# SparkFun_VoiceBox_Shield.net
KiCad netlist of a schematic drawn in EAGLE
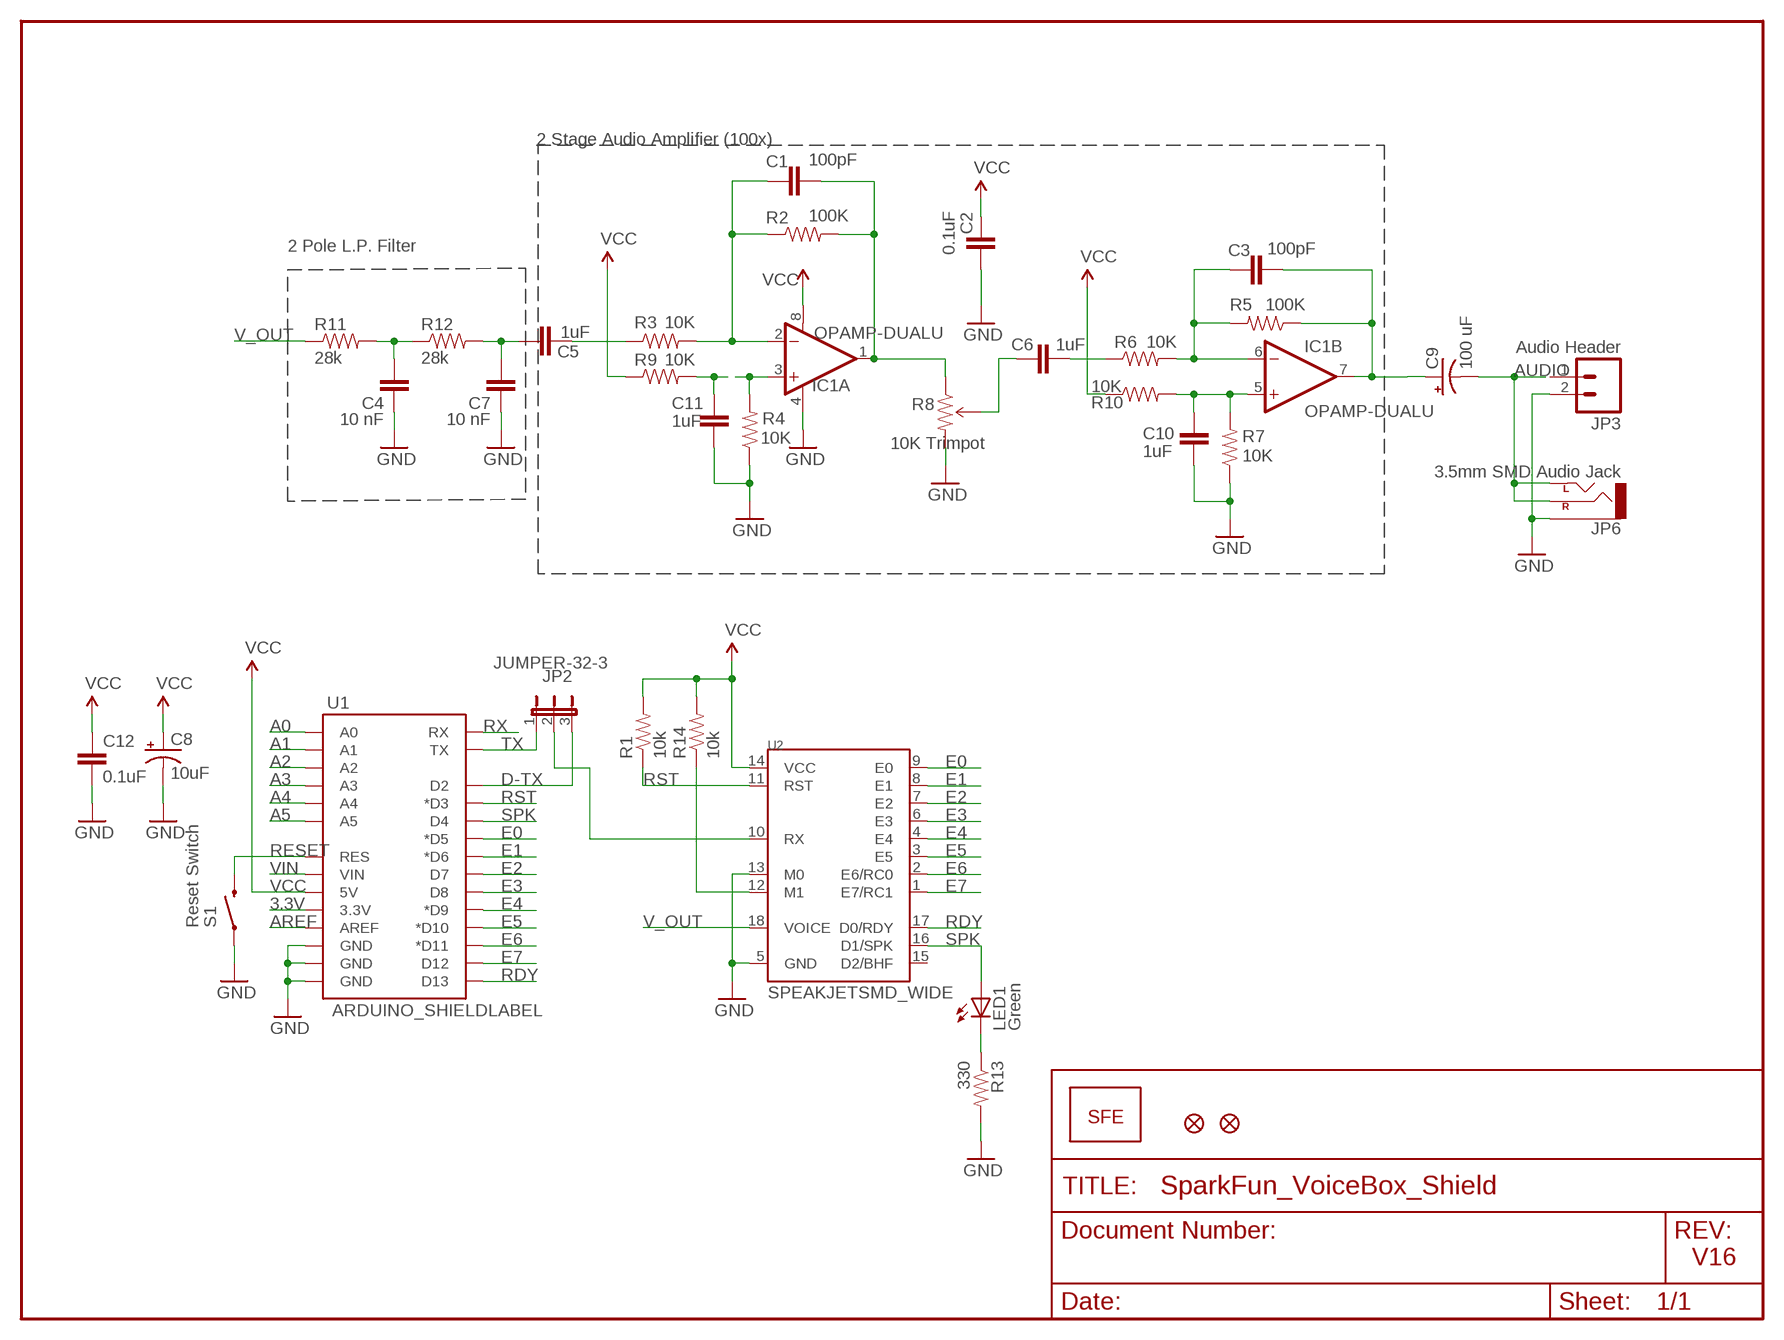
[diagram p0: schematic, sheet 1]

(export (version "E")
  (design (tool "Eeschema 10.0.6"))
  (components
    (comp (ref "C1")
      (value "100pF")
      (footprint "eagle-import:0603-CAP")
      (libsource (lib "eagle-import") (part "CAP0603-CAP"))
    )
    (comp (ref "C2")
      (value "0.1uF")
      (footprint "eagle-import:0603-CAP")
      (libsource (lib "eagle-import") (part "CAP0603-CAP"))
    )
    (comp (ref "C3")
      (value "100pF")
      (footprint "eagle-import:0603-CAP")
      (libsource (lib "eagle-import") (part "CAP0603-CAP"))
    )
    (comp (ref "C4")
      (value "10 nF")
      (footprint "eagle-import:0603-CAP")
      (libsource (lib "eagle-import") (part "CAP0603-CAP"))
    )
    (comp (ref "C5")
      (value "1uF")
      (footprint "eagle-import:0603-CAP")
      (libsource (lib "eagle-import") (part "CAP0603-CAP"))
    )
    (comp (ref "C6")
      (value "1uF")
      (footprint "eagle-import:0603-CAP")
      (libsource (lib "eagle-import") (part "CAP0603-CAP"))
    )
    (comp (ref "C7")
      (value "10 nF")
      (footprint "eagle-import:0603-CAP")
      (libsource (lib "eagle-import") (part "CAP0603-CAP"))
    )
    (comp (ref "C8")
      (value "10uF")
      (footprint "eagle-import:EIA3216")
      (libsource (lib "eagle-import") (part "CAP_POL1206"))
    )
    (comp (ref "C9")
      (value "100 uF")
      (footprint "eagle-import:EIA7343")
      (libsource (lib "eagle-import") (part "CAP_POL7343"))
    )
    (comp (ref "C10")
      (value "1uF")
      (footprint "eagle-import:0603-CAP")
      (libsource (lib "eagle-import") (part "CAP0603-CAP"))
    )
    (comp (ref "C11")
      (value "1uF")
      (footprint "eagle-import:0603-CAP")
      (libsource (lib "eagle-import") (part "CAP0603-CAP"))
    )
    (comp (ref "C12")
      (value "0.1uF")
      (footprint "eagle-import:0603-CAP")
      (libsource (lib "eagle-import") (part "CAP0603-CAP"))
    )
    (comp (ref "IC1")
      (value "OPAMP-DUALU")
      (footprint "eagle-import:SO08")
      (libsource (lib "eagle-import") (part "OPAMP-DUALU"))
    )
    (comp (ref "JP1")
      (value "LOGO-SFENEW")
      (footprint "eagle-import:SFE-NEW-WEBLOGO")
      (libsource (lib "eagle-import") (part "LOGO-SFENEW"))
    )
    (comp (ref "JP2")
      (value "JUMPER-32-3")
      (footprint "eagle-import:SJ_3_PASTE2&3")
      (libsource (lib "eagle-import") (part "JUMPER-32-3"))
    )
    (comp (ref "JP3")
      (value "Audio Header")
      (footprint "eagle-import:1X02")
      (libsource (lib "eagle-import") (part "M02PTH"))
    )
    (comp (ref "JP4")
      (value "FIDUCIAL1X2")
      (footprint "eagle-import:FIDUCIAL-1X2")
      (libsource (lib "eagle-import") (part "FIDUCIAL1X2"))
    )
    (comp (ref "JP5")
      (value "FIDUCIAL1X2")
      (footprint "eagle-import:FIDUCIAL-1X2")
      (libsource (lib "eagle-import") (part "FIDUCIAL1X2"))
    )
    (comp (ref "JP6")
      (value "3.5mm SMD Audio Jack")
      (footprint "eagle-import:AUDIO-JACK-3.5MM-SMD")
      (libsource (lib "eagle-import") (part "AUDIO-JACKSMD2"))
    )
    (comp (ref "LED1")
      (value "Green")
      (footprint "eagle-import:LED-0603")
      (libsource (lib "eagle-import") (part "LED0603"))
    )
    (comp (ref "R1")
      (value "10k")
      (footprint "eagle-import:0603-RES")
      (libsource (lib "eagle-import") (part "RESISTOR0603-RES"))
    )
    (comp (ref "R2")
      (value "100K")
      (footprint "eagle-import:0603-RES")
      (libsource (lib "eagle-import") (part "RESISTOR0603-RES"))
    )
    (comp (ref "R3")
      (value "10K")
      (footprint "eagle-import:0603-RES")
      (libsource (lib "eagle-import") (part "RESISTOR0603-RES"))
    )
    (comp (ref "R4")
      (value "10K")
      (footprint "eagle-import:0603-RES")
      (libsource (lib "eagle-import") (part "RESISTOR0603-RES"))
    )
    (comp (ref "R5")
      (value "100K")
      (footprint "eagle-import:0603-RES")
      (libsource (lib "eagle-import") (part "RESISTOR0603-RES"))
    )
    (comp (ref "R6")
      (value "10K")
      (footprint "eagle-import:0603-RES")
      (libsource (lib "eagle-import") (part "RESISTOR0603-RES"))
    )
    (comp (ref "R7")
      (value "10K")
      (footprint "eagle-import:0603-RES")
      (libsource (lib "eagle-import") (part "RESISTOR0603-RES"))
    )
    (comp (ref "R8")
      (value "10K Trimpot")
      (footprint "eagle-import:TRIMPOT-3MM")
      (libsource (lib "eagle-import") (part "TRIMPOTSMD"))
    )
    (comp (ref "R9")
      (value "10K")
      (footprint "eagle-import:0603")
      (libsource (lib "eagle-import") (part "RESISTOR0603"))
    )
    (comp (ref "R10")
      (value "10K")
      (footprint "eagle-import:0603")
      (libsource (lib "eagle-import") (part "RESISTOR0603"))
    )
    (comp (ref "R11")
      (value "28k")
      (footprint "eagle-import:0603-RES")
      (libsource (lib "eagle-import") (part "RESISTOR0603-RES"))
    )
    (comp (ref "R12")
      (value "28k")
      (footprint "eagle-import:0603-RES")
      (libsource (lib "eagle-import") (part "RESISTOR0603-RES"))
    )
    (comp (ref "R13")
      (value "330")
      (footprint "eagle-import:0603-RES")
      (libsource (lib "eagle-import") (part "RESISTOR0603-RES"))
    )
    (comp (ref "R14")
      (value "10k")
      (footprint "eagle-import:0603-RES")
      (libsource (lib "eagle-import") (part "RESISTOR0603-RES"))
    )
    (comp (ref "S1")
      (value "Reset Switch")
      (footprint "eagle-import:TACTILE_SWITCH_SMD")
      (libsource (lib "eagle-import") (part "SWITCH-MOMENTARY-2SMD"))
    )
    (comp (ref "U1")
      (value "ARDUINO_SHIELDLABEL")
      (footprint "eagle-import:DUEMILANOVE_SHIELD")
      (libsource (lib "eagle-import") (part "ARDUINO_SHIELDLABEL"))
    )
    (comp (ref "U2")
      (value "SPEAKJETSMD_WIDE")
      (footprint "eagle-import:SO-18W")
      (libsource (lib "eagle-import") (part "SPEAKJETSMD_WIDE"))
    )
  )
  (nets
    (net (code "1") (name "/3.3V") (class "Default")
      (node (ref "U1") (pin "3.3V") (pinfunction "3.3V_3.3V") (pintype "bidirectional"))
    )
    (net (code "2") (name "/A0") (class "Default")
      (node (ref "U1") (pin "A0") (pinfunction "A0_A0") (pintype "bidirectional"))
    )
    (net (code "3") (name "/A1") (class "Default")
      (node (ref "U1") (pin "A1") (pinfunction "A1_A1") (pintype "bidirectional"))
    )
    (net (code "4") (name "/A2") (class "Default")
      (node (ref "U1") (pin "A2") (pinfunction "A2_A2") (pintype "bidirectional"))
    )
    (net (code "5") (name "/A3") (class "Default")
      (node (ref "U1") (pin "A3") (pinfunction "A3_A3") (pintype "bidirectional"))
    )
    (net (code "6") (name "/A4") (class "Default")
      (node (ref "U1") (pin "A4") (pinfunction "A4_A4") (pintype "bidirectional"))
    )
    (net (code "7") (name "/A5") (class "Default")
      (node (ref "U1") (pin "A5") (pinfunction "A5_A5") (pintype "bidirectional"))
    )
    (net (code "8") (name "/AREF") (class "Default")
      (node (ref "U1") (pin "AREF") (pinfunction "AREF_AREF") (pintype "bidirectional"))
    )
    (net (code "9") (name "/AUDIO") (class "Default")
      (node (ref "C9") (pin "C") (pinfunction "-_C") (pintype "passive"))
      (node (ref "JP3") (pin "1") (pinfunction "1_1") (pintype "passive"))
      (node (ref "JP6") (pin "RING") (pinfunction "RIGHT_RING") (pintype "bidirectional"))
      (node (ref "JP6") (pin "TIP") (pinfunction "LEFT_TIP") (pintype "bidirectional"))
    )
    (net (code "10") (name "/D-TX") (class "Default")
      (node (ref "JP2") (pin "3") (pinfunction "3_3") (pintype "passive"))
      (node (ref "U1") (pin "D2") (pinfunction "D2_D2") (pintype "bidirectional"))
    )
    (net (code "11") (name "/E0") (class "Default")
      (node (ref "U1") (pin "D5") (pinfunction "*D5_D5") (pintype "bidirectional"))
      (node (ref "U2") (pin "9") (pinfunction "E0_9") (pintype "bidirectional"))
    )
    (net (code "12") (name "/E1") (class "Default")
      (node (ref "U1") (pin "D6") (pinfunction "*D6_D6") (pintype "bidirectional"))
      (node (ref "U2") (pin "8") (pinfunction "E1_8") (pintype "bidirectional"))
    )
    (net (code "13") (name "/E2") (class "Default")
      (node (ref "U1") (pin "D7") (pinfunction "D7_D7") (pintype "bidirectional"))
      (node (ref "U2") (pin "7") (pinfunction "E2_7") (pintype "bidirectional"))
    )
    (net (code "14") (name "/E3") (class "Default")
      (node (ref "U1") (pin "D8") (pinfunction "D8_D8") (pintype "bidirectional"))
      (node (ref "U2") (pin "6") (pinfunction "E3_6") (pintype "bidirectional"))
    )
    (net (code "15") (name "/E4") (class "Default")
      (node (ref "U1") (pin "D9") (pinfunction "*D9_D9") (pintype "bidirectional"))
      (node (ref "U2") (pin "4") (pinfunction "E4_4") (pintype "bidirectional"))
    )
    (net (code "16") (name "/E5") (class "Default")
      (node (ref "U1") (pin "D10") (pinfunction "*D10_D10") (pintype "bidirectional"))
      (node (ref "U2") (pin "3") (pinfunction "E5_3") (pintype "bidirectional"))
    )
    (net (code "17") (name "/E6") (class "Default")
      (node (ref "U1") (pin "D11") (pinfunction "*D11_D11") (pintype "bidirectional"))
      (node (ref "U2") (pin "2") (pinfunction "E6/RC0_2") (pintype "bidirectional"))
    )
    (net (code "18") (name "/E7") (class "Default")
      (node (ref "U1") (pin "D12") (pinfunction "D12_D12") (pintype "bidirectional"))
      (node (ref "U2") (pin "1") (pinfunction "E7/RC1_1") (pintype "bidirectional"))
    )
    (net (code "19") (name "/RDY") (class "Default")
      (node (ref "U1") (pin "D13") (pinfunction "D13_D13") (pintype "bidirectional"))
      (node (ref "U2") (pin "17") (pinfunction "D0/RDY_17") (pintype "bidirectional"))
    )
    (net (code "20") (name "/RESET") (class "Default")
      (node (ref "S1") (pin "3") (pinfunction "2_3") (pintype "passive"))
      (node (ref "U1") (pin "RES") (pinfunction "RES_RES") (pintype "bidirectional"))
    )
    (net (code "21") (name "/RST") (class "Default")
      (node (ref "R1") (pin "1") (pinfunction "1_1") (pintype "passive"))
      (node (ref "U1") (pin "D3") (pinfunction "*D3_D3") (pintype "bidirectional"))
      (node (ref "U2") (pin "11") (pinfunction "RST_11") (pintype "bidirectional"))
    )
    (net (code "22") (name "/RX") (class "Default")
      (node (ref "U1") (pin "RX") (pinfunction "RX_RX") (pintype "bidirectional"))
    )
    (net (code "23") (name "/SPK") (class "Default")
      (node (ref "LED1") (pin "A") (pinfunction "A_A") (pintype "passive"))
      (node (ref "U1") (pin "D4") (pinfunction "D4_D4") (pintype "bidirectional"))
      (node (ref "U2") (pin "16") (pinfunction "D1/SPK_16") (pintype "bidirectional"))
    )
    (net (code "24") (name "/TX") (class "Default")
      (node (ref "JP2") (pin "1") (pinfunction "1_1") (pintype "passive"))
      (node (ref "U1") (pin "TX") (pinfunction "TX_TX") (pintype "bidirectional"))
    )
    (net (code "25") (name "/VIN") (class "Default")
      (node (ref "U1") (pin "VIN") (pinfunction "VIN_VIN") (pintype "bidirectional"))
    )
    (net (code "26") (name "/V_OUT") (class "Default")
      (node (ref "R11") (pin "1") (pinfunction "1_1") (pintype "passive"))
      (node (ref "U2") (pin "18") (pinfunction "VOICE_18") (pintype "bidirectional"))
    )
    (net (code "27") (name "GND") (class "Default")
      (node (ref "C10") (pin "2") (pinfunction "2_2") (pintype "passive"))
      (node (ref "C11") (pin "2") (pinfunction "2_2") (pintype "passive"))
      (node (ref "C12") (pin "2") (pinfunction "2_2") (pintype "passive"))
      (node (ref "C2") (pin "2") (pinfunction "2_2") (pintype "passive"))
      (node (ref "C4") (pin "1") (pinfunction "1_1") (pintype "passive"))
      (node (ref "C7") (pin "1") (pinfunction "1_1") (pintype "passive"))
      (node (ref "C8") (pin "C") (pinfunction "-_C") (pintype "passive"))
      (node (ref "IC1") (pin "4") (pinfunction "V-_4") (pintype "power_in"))
      (node (ref "JP3") (pin "2") (pinfunction "2_2") (pintype "passive"))
      (node (ref "JP6") (pin "SLEEVE") (pinfunction "SLEEVE_SLEEVE") (pintype "bidirectional"))
      (node (ref "R13") (pin "2") (pinfunction "2_2") (pintype "passive"))
      (node (ref "R4") (pin "1") (pinfunction "1_1") (pintype "passive"))
      (node (ref "R7") (pin "1") (pinfunction "1_1") (pintype "passive"))
      (node (ref "R8") (pin "3") (pinfunction "CW_3") (pintype "passive"))
      (node (ref "S1") (pin "1") (pinfunction "1_1") (pintype "passive"))
      (node (ref "U1") (pin "GND@0") (pinfunction "GND_GND@0") (pintype "bidirectional"))
      (node (ref "U1") (pin "GND@1") (pinfunction "GND_GND@1") (pintype "bidirectional"))
      (node (ref "U1") (pin "GND@2") (pinfunction "GND_GND@2") (pintype "bidirectional"))
      (node (ref "U2") (pin "13") (pinfunction "M0_13") (pintype "bidirectional"))
      (node (ref "U2") (pin "5") (pinfunction "GND_5") (pintype "bidirectional"))
    )
    (net (code "28") (name "Net-(C4-Pad2)") (class "Default")
      (node (ref "C4") (pin "2") (pinfunction "2_2") (pintype "passive"))
      (node (ref "R11") (pin "2") (pinfunction "2_2") (pintype "passive"))
      (node (ref "R12") (pin "1") (pinfunction "1_1") (pintype "passive"))
    )
    (net (code "29") (name "Net-(C5-Pad1)") (class "Default")
      (node (ref "C5") (pin "1") (pinfunction "1_1") (pintype "passive"))
      (node (ref "C7") (pin "2") (pinfunction "2_2") (pintype "passive"))
      (node (ref "R12") (pin "2") (pinfunction "2_2") (pintype "passive"))
    )
    (net (code "30") (name "Net-(C5-Pad2)") (class "Default")
      (node (ref "C5") (pin "2") (pinfunction "2_2") (pintype "passive"))
      (node (ref "R3") (pin "1") (pinfunction "1_1") (pintype "passive"))
    )
    (net (code "31") (name "Net-(C6-Pad1)") (class "Default")
      (node (ref "C6") (pin "1") (pinfunction "1_1") (pintype "passive"))
      (node (ref "R6") (pin "1") (pinfunction "1_1") (pintype "passive"))
    )
    (net (code "32") (name "Net-(C9-+)") (class "Default")
      (node (ref "C3") (pin "2") (pinfunction "2_2") (pintype "passive"))
      (node (ref "C9") (pin "A") (pinfunction "+_A") (pintype "passive"))
      (node (ref "IC1") (pin "7") (pinfunction "OUT_7") (pintype "output"))
      (node (ref "R5") (pin "1") (pinfunction "1_1") (pintype "passive"))
    )
    (net (code "33") (name "Net-(IC1A-+IN)") (class "Default")
      (node (ref "C11") (pin "1") (pinfunction "1_1") (pintype "passive"))
      (node (ref "IC1") (pin "3") (pinfunction "+IN_3") (pintype "input"))
      (node (ref "R4") (pin "2") (pinfunction "2_2") (pintype "passive"))
      (node (ref "R9") (pin "2") (pinfunction "2_2") (pintype "passive"))
    )
    (net (code "34") (name "Net-(IC1A--IN)") (class "Default")
      (node (ref "C1") (pin "1") (pinfunction "1_1") (pintype "passive"))
      (node (ref "IC1") (pin "2") (pinfunction "-IN_2") (pintype "input"))
      (node (ref "R2") (pin "1") (pinfunction "1_1") (pintype "passive"))
      (node (ref "R3") (pin "2") (pinfunction "2_2") (pintype "passive"))
    )
    (net (code "35") (name "Net-(IC1A-OUT)") (class "Default")
      (node (ref "C1") (pin "2") (pinfunction "2_2") (pintype "passive"))
      (node (ref "IC1") (pin "1") (pinfunction "OUT_1") (pintype "output"))
      (node (ref "R2") (pin "2") (pinfunction "2_2") (pintype "passive"))
      (node (ref "R8") (pin "1") (pinfunction "CCW_1") (pintype "passive"))
    )
    (net (code "36") (name "Net-(IC1B-+IN)") (class "Default")
      (node (ref "C10") (pin "1") (pinfunction "1_1") (pintype "passive"))
      (node (ref "IC1") (pin "5") (pinfunction "+IN_5") (pintype "input"))
      (node (ref "R10") (pin "2") (pinfunction "2_2") (pintype "passive"))
      (node (ref "R7") (pin "2") (pinfunction "2_2") (pintype "passive"))
    )
    (net (code "37") (name "Net-(IC1B--IN)") (class "Default")
      (node (ref "C3") (pin "1") (pinfunction "1_1") (pintype "passive"))
      (node (ref "IC1") (pin "6") (pinfunction "-IN_6") (pintype "input"))
      (node (ref "R5") (pin "2") (pinfunction "2_2") (pintype "passive"))
      (node (ref "R6") (pin "2") (pinfunction "2_2") (pintype "passive"))
    )
    (net (code "38") (name "Net-(LED1-PadC)") (class "Default")
      (node (ref "LED1") (pin "C") (pinfunction "C_C") (pintype "passive"))
      (node (ref "R13") (pin "1") (pinfunction "1_1") (pintype "passive"))
    )
    (net (code "39") (name "Net-(R8-WIPER)") (class "Default")
      (node (ref "C6") (pin "2") (pinfunction "2_2") (pintype "passive"))
      (node (ref "R8") (pin "2") (pinfunction "WIPER_2") (pintype "passive"))
    )
    (net (code "40") (name "Net-(U2-M1)") (class "Default")
      (node (ref "R14") (pin "1") (pinfunction "1_1") (pintype "passive"))
      (node (ref "U2") (pin "12") (pinfunction "M1_12") (pintype "bidirectional"))
    )
    (net (code "41") (name "Net-(U2-RX)") (class "Default")
      (node (ref "JP2") (pin "2") (pinfunction "2_2") (pintype "passive"))
      (node (ref "U2") (pin "10") (pinfunction "RX_10") (pintype "bidirectional"))
    )
    (net (code "42") (name "VCC") (class "Default")
      (node (ref "C12") (pin "1") (pinfunction "1_1") (pintype "passive"))
      (node (ref "C2") (pin "1") (pinfunction "1_1") (pintype "passive"))
      (node (ref "C8") (pin "A") (pinfunction "+_A") (pintype "passive"))
      (node (ref "IC1") (pin "8") (pinfunction "V+_8") (pintype "power_in"))
      (node (ref "R1") (pin "2") (pinfunction "2_2") (pintype "passive"))
      (node (ref "R10") (pin "1") (pinfunction "1_1") (pintype "passive"))
      (node (ref "R14") (pin "2") (pinfunction "2_2") (pintype "passive"))
      (node (ref "R9") (pin "1") (pinfunction "1_1") (pintype "passive"))
      (node (ref "U1") (pin "5V") (pinfunction "5V_5V") (pintype "bidirectional"))
      (node (ref "U2") (pin "14") (pinfunction "VCC_14") (pintype "bidirectional"))
    )
    (net (code "43") (name "unconnected-(U2-D2{slash}BHF-Pad15)") (class "Default")
      (node (ref "U2") (pin "15") (pinfunction "D2/BHF_15") (pintype "bidirectional"))
    )
  )
)
